# PAGE3.net
KiCad netlist of a schematic drawn in Altium Designer
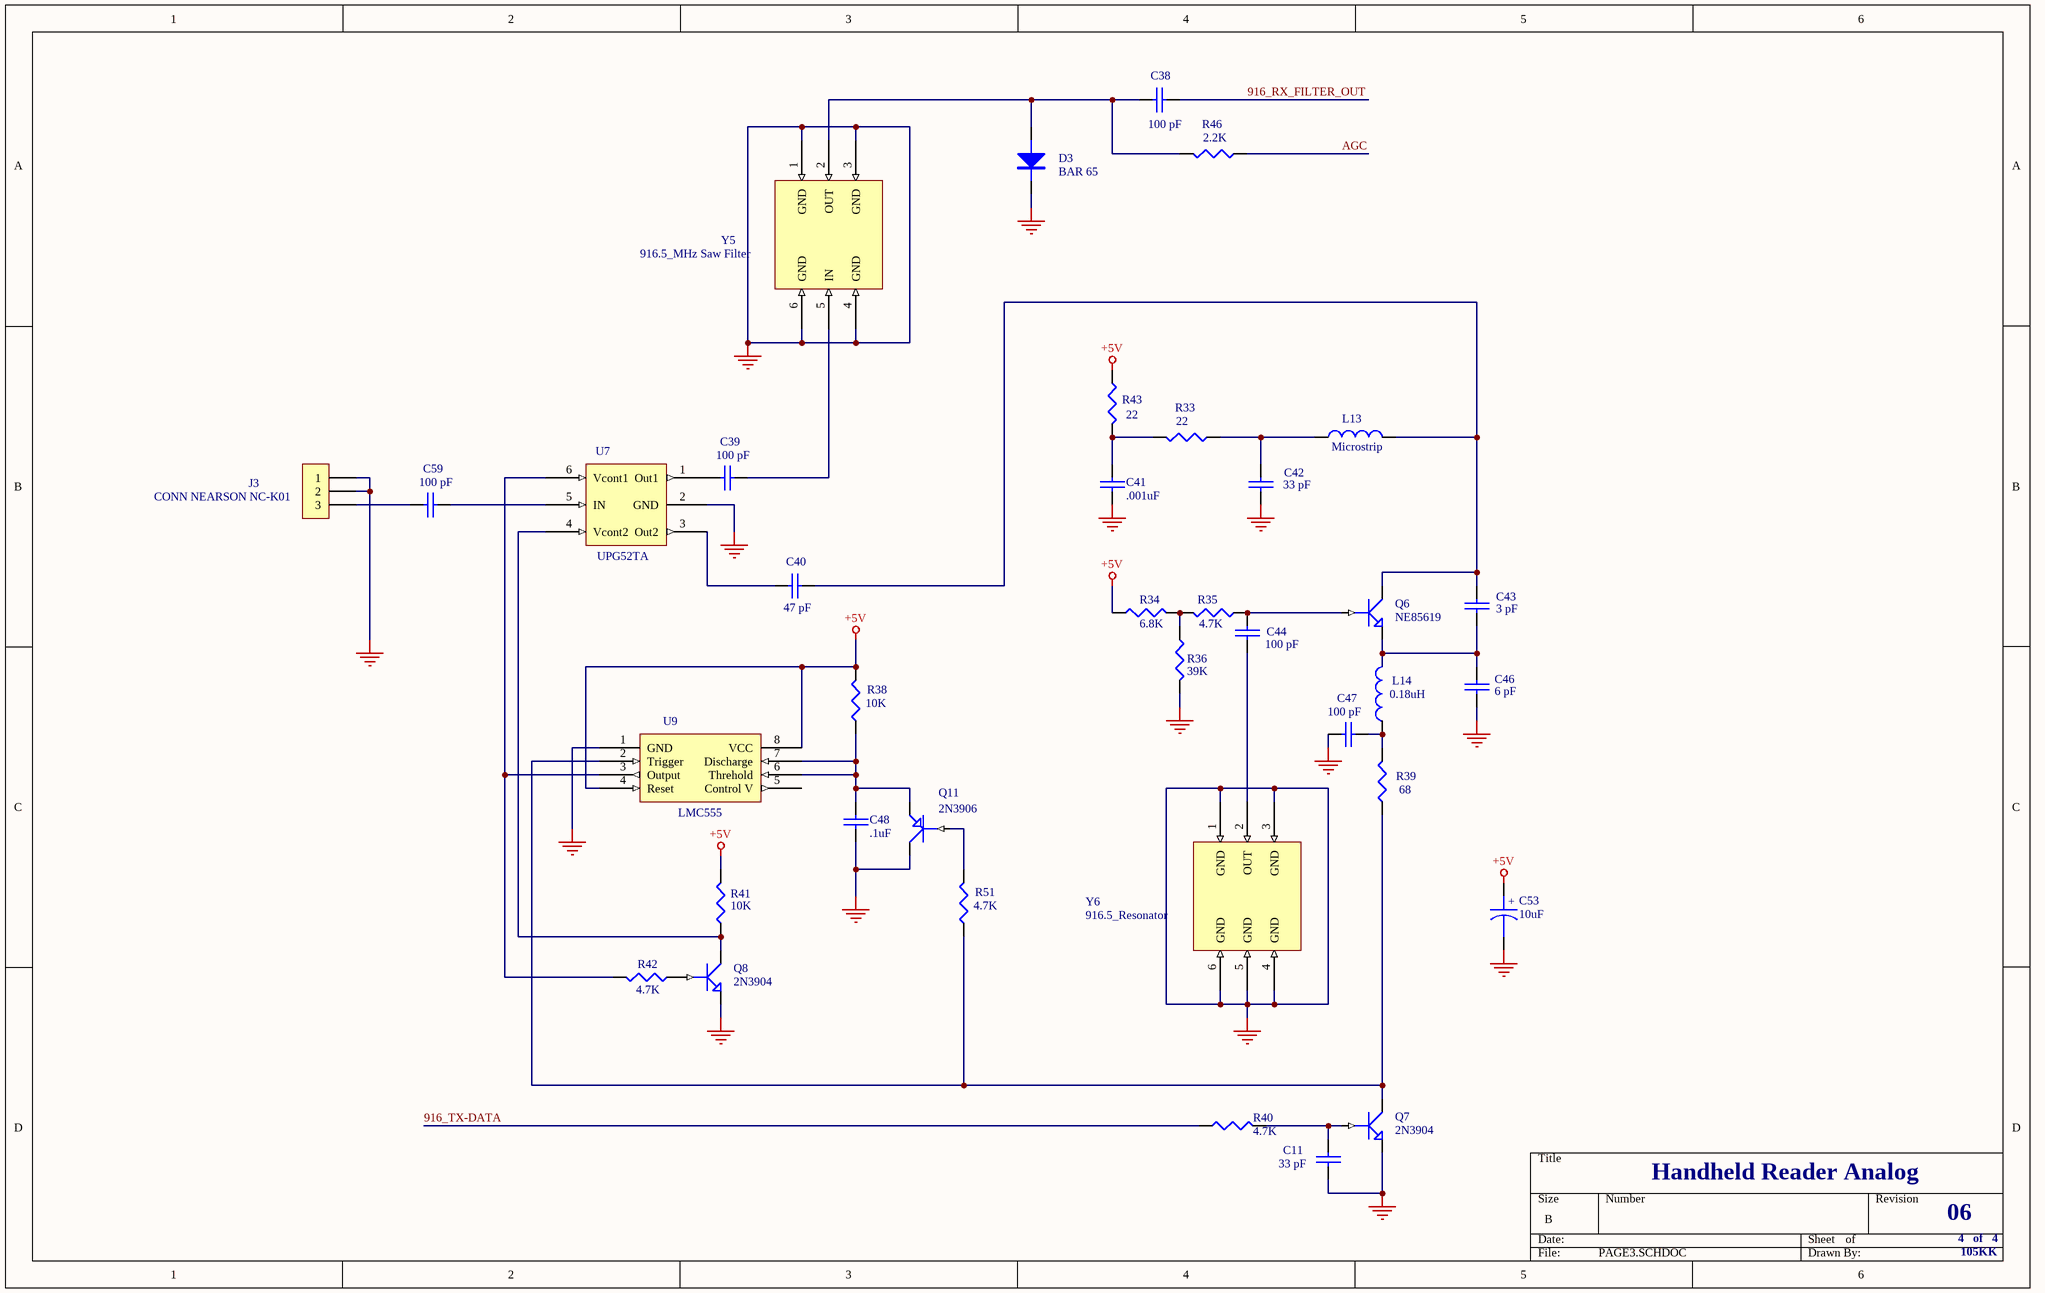
[diagram p0: PAGE3.SCHDOC]

(export (version "E")
  (design (tool "Eeschema 10.0.6"))
  (components
    (comp (ref "C11")
      (value "33 pF")
      (footprint "0603")
      (description "Capacitor")
      (libsource (lib "*") (part "CAP"))
    )
    (comp (ref "C38")
      (value "100 pF")
      (footprint "0603")
      (description "Capacitor")
      (libsource (lib "*") (part "CAP"))
    )
    (comp (ref "C39")
      (value "100 pF")
      (footprint "0603")
      (description "Capacitor")
      (libsource (lib "*") (part "CAP"))
    )
    (comp (ref "C40")
      (value "47 pF")
      (footprint "0603")
      (description "Capacitor")
      (libsource (lib "*") (part "CAP"))
    )
    (comp (ref "C41")
      (value ".001uF")
      (footprint "0603")
      (description "Capacitor")
      (libsource (lib "*") (part "CAP"))
    )
    (comp (ref "C42")
      (value "33 pF")
      (footprint "0603")
      (description "Capacitor")
      (libsource (lib "*") (part "CAP"))
    )
    (comp (ref "C43")
      (value "3 pF")
      (footprint "0603")
      (description "Capacitor")
      (libsource (lib "*") (part "CAP"))
    )
    (comp (ref "C44")
      (value "100 pF")
      (footprint "0603")
      (description "Capacitor")
      (libsource (lib "*") (part "CAP"))
    )
    (comp (ref "C46")
      (value "6 pF")
      (footprint "0603")
      (description "Capacitor")
      (libsource (lib "*") (part "CAP"))
    )
    (comp (ref "C47")
      (value "100 pF")
      (footprint "0603")
      (description "Capacitor")
      (libsource (lib "*") (part "CAP"))
    )
    (comp (ref "C48")
      (value ".1uF")
      (footprint "0603")
      (description "Capacitor")
      (libsource (lib "*") (part "CAP"))
    )
    (comp (ref "C53")
      (value "10uF")
      (footprint "CAP A CASE")
      (description "Capacitor")
      (libsource (lib "*") (part "CAPACITOR POL"))
    )
    (comp (ref "C59")
      (value "100 pF")
      (footprint "0603")
      (description "Capacitor")
      (libsource (lib "*") (part "CAP"))
    )
    (comp (ref "D3")
      (value "BAR 65")
      (footprint "DIODE SC79")
      (description "Diode")
      (libsource (lib "*") (part "DIODE"))
    )
    (comp (ref "J3")
      (value "CONN NEARSON NC-K01")
      (footprint "CONN NEARSON NC-K01")
      (description "Connector")
      (libsource (lib "*") (part "CON3"))
    )
    (comp (ref "L13") (value "Microstrip") (footprint "MICROSTRIP") (libsource (lib "*") (part "INDUCTOR")))
    (comp (ref "L14") (value "0.18uH") (footprint "0603") (libsource (lib "*") (part "INDUCTOR")))
    (comp (ref "Q6")
      (value "NE85619")
      (footprint "3 PIN ULTRA SUPER MINI MOLD")
      (description "NPN Transistor")
      (libsource (lib "*") (part "NPN1"))
    )
    (comp (ref "Q7")
      (value "2N3904")
      (footprint "SOT23 TRANS")
      (description "NPN Transistor")
      (libsource (lib "*") (part "NPN1"))
    )
    (comp (ref "Q8")
      (value "2N3904")
      (footprint "SOT23 TRANS")
      (description "NPN Transistor")
      (libsource (lib "*") (part "NPN1"))
    )
    (comp (ref "Q11")
      (value "2N3906")
      (footprint "SOT23 TRANS")
      (description "PNP Transistor")
      (libsource (lib "*") (part "PNP1"))
    )
    (comp (ref "R33") (value "22") (footprint "0603") (libsource (lib "*") (part "RESISTOR")))
    (comp (ref "R34") (value "6.8K") (footprint "0603") (libsource (lib "*") (part "RESISTOR")))
    (comp (ref "R35") (value "4.7K") (footprint "0603") (libsource (lib "*") (part "RESISTOR")))
    (comp (ref "R36") (value "39K") (footprint "0603") (libsource (lib "*") (part "RESISTOR")))
    (comp (ref "R38") (value "10K") (footprint "0603") (libsource (lib "*") (part "RESISTOR")))
    (comp (ref "R39") (value "68") (footprint "0603") (libsource (lib "*") (part "RESISTOR")))
    (comp (ref "R40") (value "4.7K") (footprint "0603") (libsource (lib "*") (part "RESISTOR")))
    (comp (ref "R41") (value "10K") (footprint "0603") (libsource (lib "*") (part "RESISTOR")))
    (comp (ref "R42") (value "4.7K") (footprint "0603") (libsource (lib "*") (part "RESISTOR")))
    (comp (ref "R43") (value "22") (footprint "0603") (libsource (lib "*") (part "RESISTOR")))
    (comp (ref "R46") (value "2.2K") (footprint "0603") (libsource (lib "*") (part "RESISTOR")))
    (comp (ref "R51") (value "4.7K") (footprint "0603") (libsource (lib "*") (part "RESISTOR")))
    (comp (ref "U7") (value "UPG52TA") (footprint "TO6") (libsource (lib "*") (part "UPG152TA_0")))
    (comp (ref "U9") (value "LMC555") (footprint "SO8 SMALL") (libsource (lib "*") (part "LMC555")))
    (comp (ref "Y5") (value "916.5_MHz Saw Filter") (libsource (lib "*") (part "RESONATOR3")))
    (comp (ref "Y6")
      (value "916.5_Resonator")
      (footprint "RESONATOR2")
      (libsource (lib "*") (part "RESONATOR2"))
    )
  )
  (nets
    (net (code "1") (name "+5V") (class "Default")
      (node (ref "C53") (pin "1") (pinfunction "1_1") (pintype "passive"))
      (node (ref "R34") (pin "1") (pinfunction "1_1") (pintype "passive"))
      (node (ref "R38") (pin "2") (pinfunction "2_2") (pintype "passive"))
      (node (ref "R41") (pin "2") (pinfunction "2_2") (pintype "passive"))
      (node (ref "R43") (pin "1") (pinfunction "1_1") (pintype "passive"))
      (node (ref "U9") (pin "4") (pinfunction "Reset_4") (pintype "input"))
      (node (ref "U9") (pin "8") (pinfunction "VCC_8") (pintype "power_in"))
    )
    (net (code "2") (name "/916_RX_FILTER_OUT") (class "Default")
      (node (ref "C38") (pin "2") (pinfunction "2_2") (pintype "passive"))
    )
    (net (code "3") (name "/916_TX-DATA") (class "Default")
      (node (ref "R40") (pin "1") (pinfunction "1_1") (pintype "passive"))
    )
    (net (code "4") (name "/AGC") (class "Default")
      (node (ref "R46") (pin "1") (pinfunction "1_1") (pintype "passive"))
    )
    (net (code "5") (name "GND_SIGNAL") (class "Default")
      (node (ref "C11") (pin "2") (pinfunction "2_2") (pintype "passive"))
      (node (ref "C41") (pin "2") (pinfunction "2_2") (pintype "passive"))
      (node (ref "C42") (pin "2") (pinfunction "2_2") (pintype "passive"))
      (node (ref "C46") (pin "2") (pinfunction "2_2") (pintype "passive"))
      (node (ref "C47") (pin "1") (pinfunction "1_1") (pintype "passive"))
      (node (ref "C48") (pin "2") (pinfunction "2_2") (pintype "passive"))
      (node (ref "C53") (pin "2") (pinfunction "2_2") (pintype "passive"))
      (node (ref "D3") (pin "K") (pinfunction "K_K") (pintype "passive"))
      (node (ref "J3") (pin "1") (pinfunction "1_1") (pintype "passive"))
      (node (ref "J3") (pin "2") (pinfunction "2_2") (pintype "passive"))
      (node (ref "Q11") (pin "C") (pinfunction "C_C") (pintype "passive"))
      (node (ref "Q7") (pin "E") (pinfunction "E_E") (pintype "passive"))
      (node (ref "Q8") (pin "E") (pinfunction "E_E") (pintype "passive"))
      (node (ref "R36") (pin "2") (pinfunction "2_2") (pintype "passive"))
      (node (ref "U7") (pin "2") (pinfunction "GND_2") (pintype "power_in"))
      (node (ref "U9") (pin "1") (pinfunction "GND_1") (pintype "power_in"))
      (node (ref "Y5") (pin "1") (pinfunction "GND_1") (pintype "input"))
      (node (ref "Y5") (pin "3") (pinfunction "GND_3") (pintype "input"))
      (node (ref "Y5") (pin "4") (pinfunction "GND_4") (pintype "input"))
      (node (ref "Y5") (pin "6") (pinfunction "GND_6") (pintype "input"))
      (node (ref "Y6") (pin "1") (pinfunction "GND_1") (pintype "input"))
      (node (ref "Y6") (pin "3") (pinfunction "GND_3") (pintype "input"))
      (node (ref "Y6") (pin "4") (pinfunction "GND_4") (pintype "input"))
      (node (ref "Y6") (pin "5") (pinfunction "GND_5") (pintype "input"))
      (node (ref "Y6") (pin "6") (pinfunction "GND_6") (pintype "input"))
    )
    (net (code "6") (name "Net-(C11-Pad1)") (class "Default")
      (node (ref "C11") (pin "1") (pinfunction "1_1") (pintype "passive"))
      (node (ref "Q7") (pin "B") (pinfunction "B_B") (pintype "input"))
      (node (ref "R40") (pin "2") (pinfunction "2_2") (pintype "passive"))
    )
    (net (code "7") (name "Net-(C40-Pad2)") (class "Default")
      (node (ref "C40") (pin "2") (pinfunction "2_2") (pintype "passive"))
      (node (ref "C43") (pin "1") (pinfunction "1_1") (pintype "passive"))
      (node (ref "L13") (pin "2") (pinfunction "2_2") (pintype "passive"))
      (node (ref "Q6") (pin "C") (pinfunction "C_C") (pintype "passive"))
    )
    (net (code "8") (name "Net-(C41-Pad1)") (class "Default")
      (node (ref "C41") (pin "1") (pinfunction "1_1") (pintype "passive"))
      (node (ref "R33") (pin "2") (pinfunction "2_2") (pintype "passive"))
      (node (ref "R43") (pin "2") (pinfunction "2_2") (pintype "passive"))
    )
    (net (code "9") (name "Net-(C42-Pad1)") (class "Default")
      (node (ref "C42") (pin "1") (pinfunction "1_1") (pintype "passive"))
      (node (ref "L13") (pin "1") (pinfunction "1_1") (pintype "passive"))
      (node (ref "R33") (pin "1") (pinfunction "1_1") (pintype "passive"))
    )
    (net (code "10") (name "Net-(C43-Pad2)") (class "Default")
      (node (ref "C43") (pin "2") (pinfunction "2_2") (pintype "passive"))
      (node (ref "C46") (pin "1") (pinfunction "1_1") (pintype "passive"))
      (node (ref "L14") (pin "2") (pinfunction "2_2") (pintype "passive"))
      (node (ref "Q6") (pin "E") (pinfunction "E_E") (pintype "passive"))
    )
    (net (code "11") (name "Net-(C44-Pad1)") (class "Default")
      (node (ref "C44") (pin "1") (pinfunction "1_1") (pintype "passive"))
      (node (ref "Q6") (pin "B") (pinfunction "B_B") (pintype "input"))
      (node (ref "R35") (pin "1") (pinfunction "1_1") (pintype "passive"))
    )
    (net (code "12") (name "Net-(C47-Pad2)") (class "Default")
      (node (ref "C47") (pin "2") (pinfunction "2_2") (pintype "passive"))
      (node (ref "L14") (pin "1") (pinfunction "1_1") (pintype "passive"))
      (node (ref "R39") (pin "2") (pinfunction "2_2") (pintype "passive"))
    )
    (net (code "13") (name "Net-(C59-Pad1)") (class "Default")
      (node (ref "C59") (pin "1") (pinfunction "1_1") (pintype "passive"))
      (node (ref "J3") (pin "3") (pinfunction "3_3") (pintype "passive"))
    )
    (net (code "14") (name "Net-(Q8-PadB)") (class "Default")
      (node (ref "Q8") (pin "B") (pinfunction "B_B") (pintype "input"))
      (node (ref "R42") (pin "1") (pinfunction "1_1") (pintype "passive"))
    )
    (net (code "15") (name "Net-(Q11-PadB)") (class "Default")
      (node (ref "Q11") (pin "B") (pinfunction "B_B") (pintype "input"))
      (node (ref "R51") (pin "2") (pinfunction "2_2") (pintype "passive"))
    )
    (net (code "16") (name "Net-(R34-Pad2)") (class "Default")
      (node (ref "R34") (pin "2") (pinfunction "2_2") (pintype "passive"))
      (node (ref "R35") (pin "2") (pinfunction "2_2") (pintype "passive"))
      (node (ref "R36") (pin "1") (pinfunction "1_1") (pintype "passive"))
    )
    (net (code "17") (name "Net-(U7-IN)") (class "Default")
      (node (ref "C59") (pin "2") (pinfunction "2_2") (pintype "passive"))
      (node (ref "U7") (pin "5") (pinfunction "IN_5") (pintype "input"))
    )
    (net (code "18") (name "Net-(U7-Out1)") (class "Default")
      (node (ref "C39") (pin "1") (pinfunction "1_1") (pintype "passive"))
      (node (ref "U7") (pin "1") (pinfunction "Out1_1") (pintype "output"))
    )
    (net (code "19") (name "Net-(U7-Out2)") (class "Default")
      (node (ref "C40") (pin "1") (pinfunction "1_1") (pintype "passive"))
      (node (ref "U7") (pin "3") (pinfunction "Out2_3") (pintype "output"))
    )
    (net (code "20") (name "Net-(U7-Vcont1)") (class "Default")
      (node (ref "R42") (pin "2") (pinfunction "2_2") (pintype "passive"))
      (node (ref "U7") (pin "6") (pinfunction "Vcont1_6") (pintype "input"))
      (node (ref "U9") (pin "3") (pinfunction "Output_3") (pintype "output"))
    )
    (net (code "21") (name "Net-(U7-Vcont2)") (class "Default")
      (node (ref "Q8") (pin "C") (pinfunction "C_C") (pintype "passive"))
      (node (ref "R41") (pin "1") (pinfunction "1_1") (pintype "passive"))
      (node (ref "U7") (pin "4") (pinfunction "Vcont2_4") (pintype "input"))
    )
    (net (code "22") (name "Net-(U9-Discharge)") (class "Default")
      (node (ref "C48") (pin "1") (pinfunction "1_1") (pintype "passive"))
      (node (ref "Q11") (pin "E") (pinfunction "E_E") (pintype "passive"))
      (node (ref "R38") (pin "1") (pinfunction "1_1") (pintype "passive"))
      (node (ref "U9") (pin "6") (pinfunction "Threhold_6") (pintype "input"))
      (node (ref "U9") (pin "7") (pinfunction "Discharge_7") (pintype "input"))
    )
    (net (code "23") (name "Net-(U9-Trigger)") (class "Default")
      (node (ref "Q7") (pin "C") (pinfunction "C_C") (pintype "passive"))
      (node (ref "R39") (pin "1") (pinfunction "1_1") (pintype "passive"))
      (node (ref "R51") (pin "1") (pinfunction "1_1") (pintype "passive"))
      (node (ref "U9") (pin "2") (pinfunction "Trigger_2") (pintype "input"))
    )
    (net (code "24") (name "Net-(Y5-IN)") (class "Default")
      (node (ref "C39") (pin "2") (pinfunction "2_2") (pintype "passive"))
      (node (ref "Y5") (pin "5") (pinfunction "IN_5") (pintype "input"))
    )
    (net (code "25") (name "Net-(Y5-OUT)") (class "Default")
      (node (ref "C38") (pin "1") (pinfunction "1_1") (pintype "passive"))
      (node (ref "D3") (pin "A") (pinfunction "A_A") (pintype "passive"))
      (node (ref "R46") (pin "2") (pinfunction "2_2") (pintype "passive"))
      (node (ref "Y5") (pin "2") (pinfunction "OUT_2") (pintype "input"))
    )
    (net (code "26") (name "Net-(Y6-OUT)") (class "Default")
      (node (ref "C44") (pin "2") (pinfunction "2_2") (pintype "passive"))
      (node (ref "Y6") (pin "2") (pinfunction "OUT_2") (pintype "input"))
    )
    (net (code "27") (name "unconnected-(U9-Control_V-Pad5)") (class "Default")
      (node (ref "U9") (pin "5") (pinfunction "Control_V_5") (pintype "output"))
    )
  )
)
